# leddriverx3.net
KiCad netlist of a schematic drawn in EAGLE
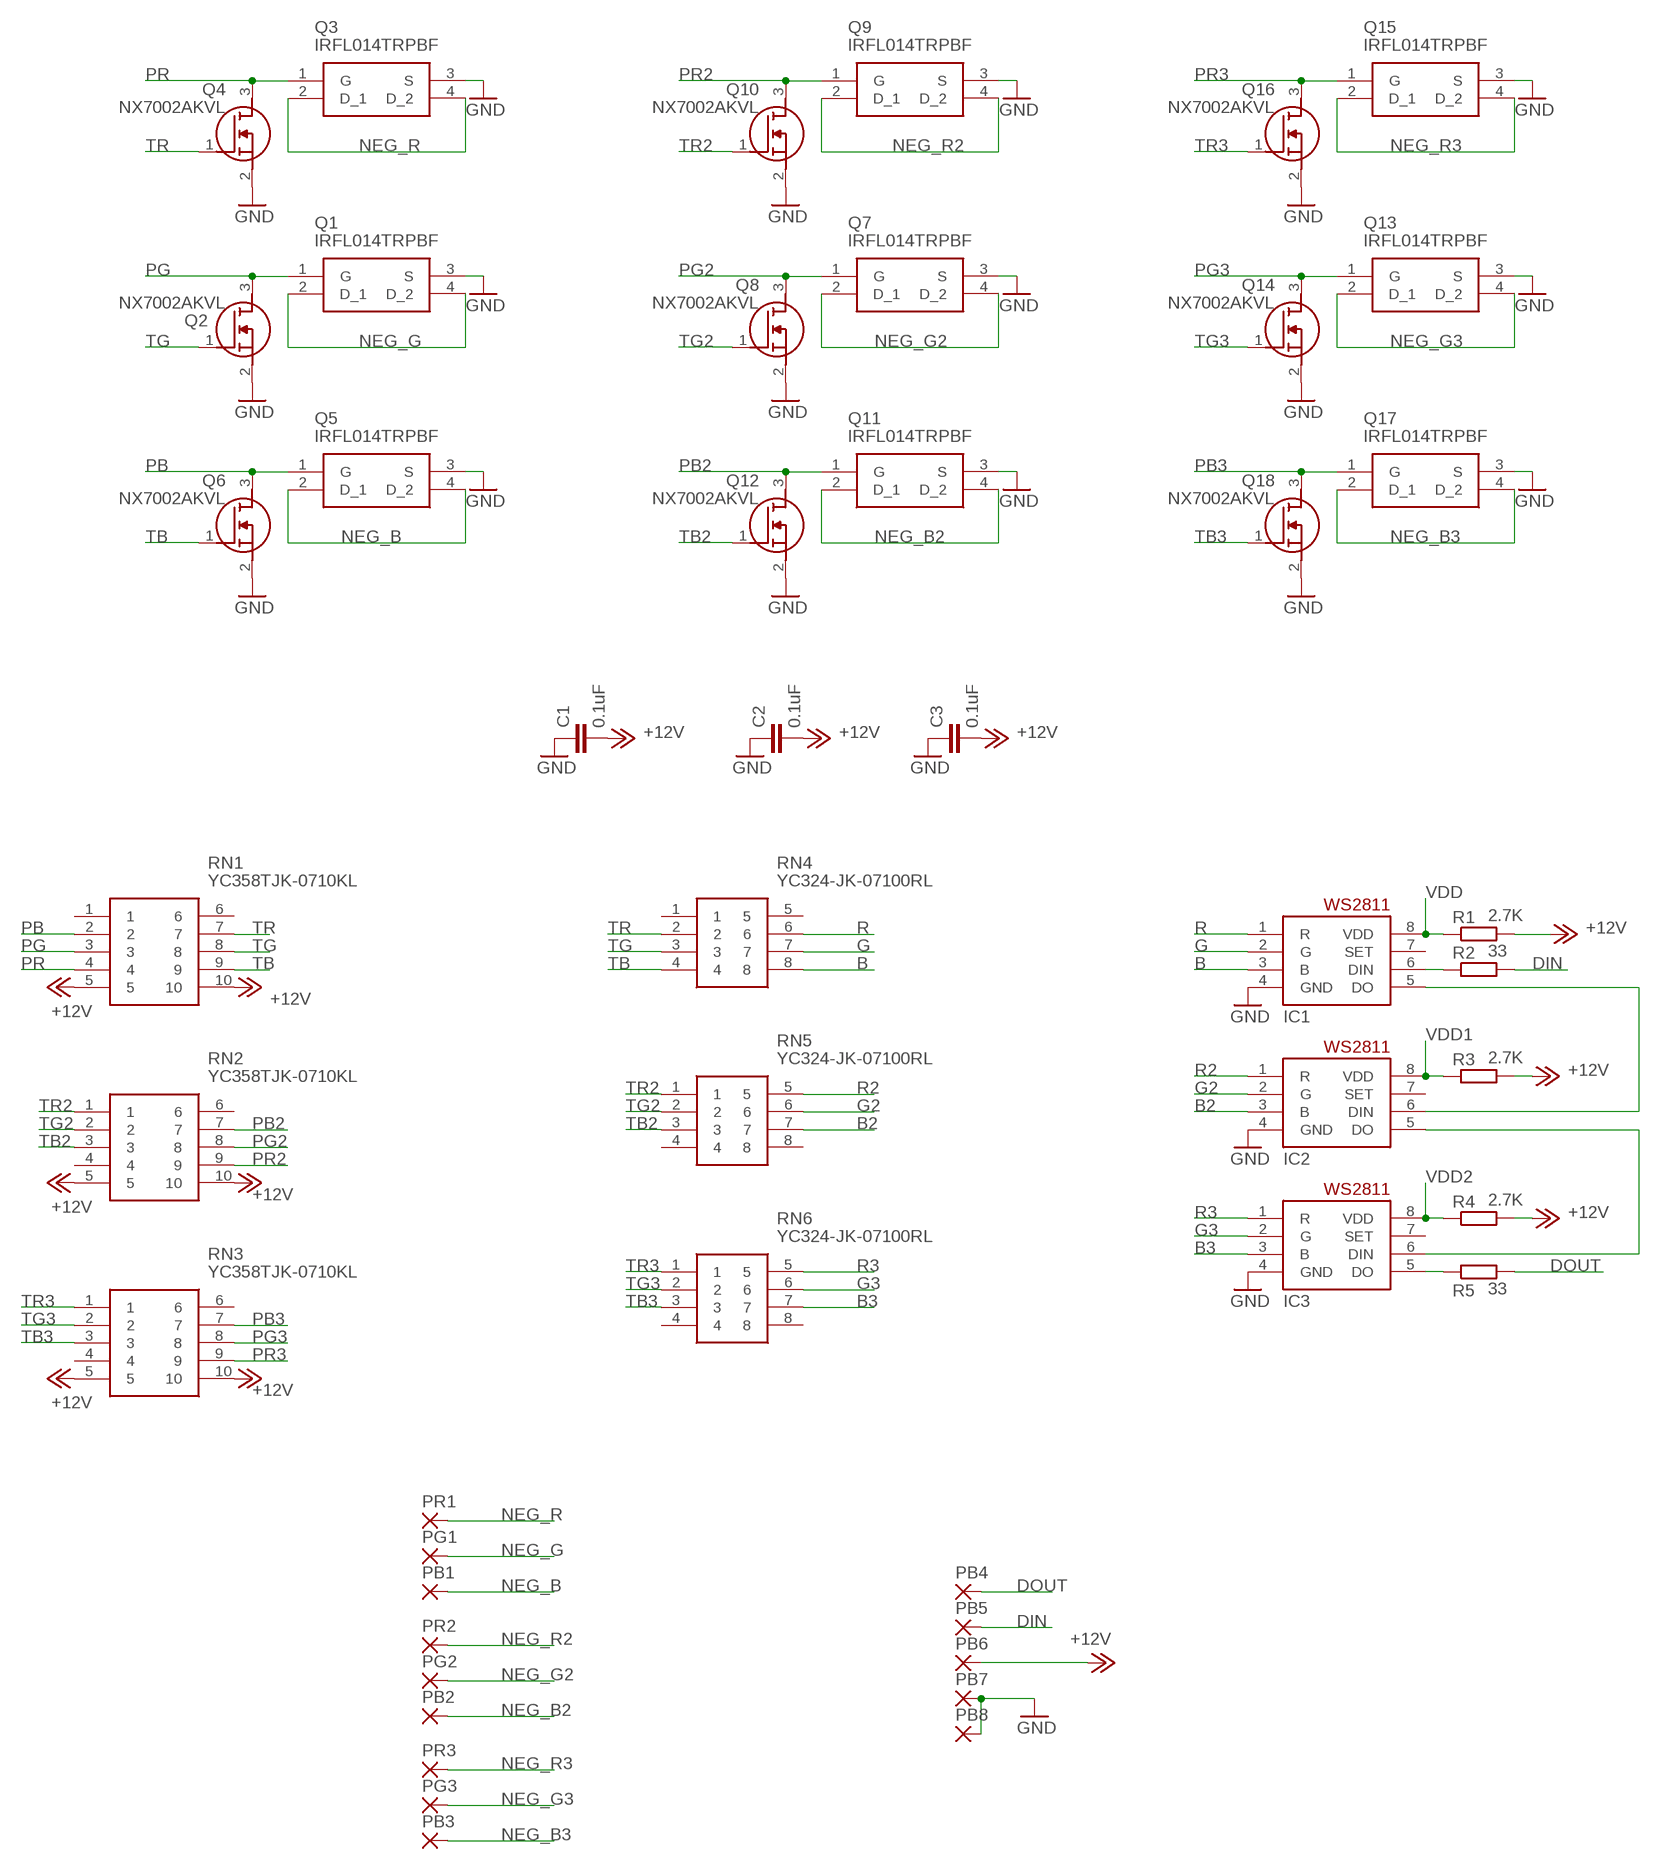
[diagram p0: schematic, sheet 1]

(export (version "E")
  (design (tool "Eeschema 10.0.6"))
  (components
    (comp (ref "C1")
      (value "0.1uF")
      (footprint "eagle-import:C1206")
      (libsource (lib "eagle-import") (part "C-EUC1206"))
    )
    (comp (ref "C2")
      (value "0.1uF")
      (footprint "eagle-import:C1206")
      (libsource (lib "eagle-import") (part "C-EUC1206"))
    )
    (comp (ref "C3")
      (value "0.1uF")
      (footprint "eagle-import:C1206")
      (libsource (lib "eagle-import") (part "C-EUC1206"))
    )
    (comp (ref "IC1")
      (value "WS2811-SOP8")
      (footprint "eagle-import:SO08-SKINNYPADS")
      (libsource (lib "eagle-import") (part "WS2811-SOP8"))
    )
    (comp (ref "IC2")
      (value "WS2811-SOP8")
      (footprint "eagle-import:SO08-SKINNYPADS")
      (libsource (lib "eagle-import") (part "WS2811-SOP8"))
    )
    (comp (ref "IC3")
      (value "WS2811-SOP8")
      (footprint "eagle-import:SO08-SKINNYPADS")
      (libsource (lib "eagle-import") (part "WS2811-SOP8"))
    )
    (comp (ref "PB1")
      (value "3,81/1,4")
      (footprint "eagle-import:3,81_1,4")
      (libsource (lib "eagle-import") (part "3,81/1,4"))
    )
    (comp (ref "PB2")
      (value "3,81/1,4")
      (footprint "eagle-import:3,81_1,4")
      (libsource (lib "eagle-import") (part "3,81/1,4"))
    )
    (comp (ref "PB3")
      (value "3,81/1,4")
      (footprint "eagle-import:3,81_1,4")
      (libsource (lib "eagle-import") (part "3,81/1,4"))
    )
    (comp (ref "PB4")
      (value "3,81/1,4")
      (footprint "eagle-import:3,81_1,4")
      (libsource (lib "eagle-import") (part "3,81/1,4"))
    )
    (comp (ref "PB5")
      (value "3,81/1,4")
      (footprint "eagle-import:3,81_1,4")
      (libsource (lib "eagle-import") (part "3,81/1,4"))
    )
    (comp (ref "PB6")
      (value "3,81/1,4")
      (footprint "eagle-import:3,81_1,4")
      (libsource (lib "eagle-import") (part "3,81/1,4"))
    )
    (comp (ref "PB7")
      (value "3,81/1,4")
      (footprint "eagle-import:3,81_1,4")
      (libsource (lib "eagle-import") (part "3,81/1,4"))
    )
    (comp (ref "PB8")
      (value "3,81/1,4")
      (footprint "eagle-import:3,81_1,4")
      (libsource (lib "eagle-import") (part "3,81/1,4"))
    )
    (comp (ref "PG1")
      (value "3,81/1,4")
      (footprint "eagle-import:3,81_1,4")
      (libsource (lib "eagle-import") (part "3,81/1,4"))
    )
    (comp (ref "PG2")
      (value "3,81/1,4")
      (footprint "eagle-import:3,81_1,4")
      (libsource (lib "eagle-import") (part "3,81/1,4"))
    )
    (comp (ref "PG3")
      (value "3,81/1,4")
      (footprint "eagle-import:3,81_1,4")
      (libsource (lib "eagle-import") (part "3,81/1,4"))
    )
    (comp (ref "PR1")
      (value "3,81/1,4")
      (footprint "eagle-import:3,81_1,4")
      (libsource (lib "eagle-import") (part "3,81/1,4"))
    )
    (comp (ref "PR2")
      (value "3,81/1,4")
      (footprint "eagle-import:3,81_1,4")
      (libsource (lib "eagle-import") (part "3,81/1,4"))
    )
    (comp (ref "PR3")
      (value "3,81/1,4")
      (footprint "eagle-import:3,81_1,4")
      (libsource (lib "eagle-import") (part "3,81/1,4"))
    )
    (comp (ref "Q1")
      (value "IRFL014TRPBF")
      (footprint "eagle-import:SOT230P700X180-4N")
      (fields (field (name "MOUSER_PART_NUMBER") "844-IRFL014TRPBF"))
      (libsource (lib "eagle-import") (part "IRFL014TRPBF"))
    )
    (comp (ref "Q2")
      (value "NX7002AKVL")
      (footprint "eagle-import:SOT95P230X110-3N")
      (fields (field (name "MOUSER_PART_NUMBER") "771-NX7002AKVL"))
      (libsource (lib "eagle-import") (part "NX7002AKVL"))
    )
    (comp (ref "Q3")
      (value "IRFL014TRPBF")
      (footprint "eagle-import:SOT230P700X180-4N")
      (fields (field (name "MOUSER_PART_NUMBER") "844-IRFL014TRPBF"))
      (libsource (lib "eagle-import") (part "IRFL014TRPBF"))
    )
    (comp (ref "Q4")
      (value "NX7002AKVL")
      (footprint "eagle-import:SOT95P230X110-3N")
      (fields (field (name "MOUSER_PART_NUMBER") "771-NX7002AKVL"))
      (libsource (lib "eagle-import") (part "NX7002AKVL"))
    )
    (comp (ref "Q5")
      (value "IRFL014TRPBF")
      (footprint "eagle-import:SOT230P700X180-4N")
      (fields (field (name "MOUSER_PART_NUMBER") "844-IRFL014TRPBF"))
      (libsource (lib "eagle-import") (part "IRFL014TRPBF"))
    )
    (comp (ref "Q6")
      (value "NX7002AKVL")
      (footprint "eagle-import:SOT95P230X110-3N")
      (fields (field (name "MOUSER_PART_NUMBER") "771-NX7002AKVL"))
      (libsource (lib "eagle-import") (part "NX7002AKVL"))
    )
    (comp (ref "Q7")
      (value "IRFL014TRPBF")
      (footprint "eagle-import:SOT230P700X180-4N")
      (fields (field (name "MOUSER_PART_NUMBER") "844-IRFL014TRPBF"))
      (libsource (lib "eagle-import") (part "IRFL014TRPBF"))
    )
    (comp (ref "Q8")
      (value "NX7002AKVL")
      (footprint "eagle-import:SOT95P230X110-3N")
      (fields (field (name "MOUSER_PART_NUMBER") "771-NX7002AKVL"))
      (libsource (lib "eagle-import") (part "NX7002AKVL"))
    )
    (comp (ref "Q9")
      (value "IRFL014TRPBF")
      (footprint "eagle-import:SOT230P700X180-4N")
      (fields (field (name "MOUSER_PART_NUMBER") "844-IRFL014TRPBF"))
      (libsource (lib "eagle-import") (part "IRFL014TRPBF"))
    )
    (comp (ref "Q10")
      (value "NX7002AKVL")
      (footprint "eagle-import:SOT95P230X110-3N")
      (fields (field (name "MOUSER_PART_NUMBER") "771-NX7002AKVL"))
      (libsource (lib "eagle-import") (part "NX7002AKVL"))
    )
    (comp (ref "Q11")
      (value "IRFL014TRPBF")
      (footprint "eagle-import:SOT230P700X180-4N")
      (fields (field (name "MOUSER_PART_NUMBER") "844-IRFL014TRPBF"))
      (libsource (lib "eagle-import") (part "IRFL014TRPBF"))
    )
    (comp (ref "Q12")
      (value "NX7002AKVL")
      (footprint "eagle-import:SOT95P230X110-3N")
      (fields (field (name "MOUSER_PART_NUMBER") "771-NX7002AKVL"))
      (libsource (lib "eagle-import") (part "NX7002AKVL"))
    )
    (comp (ref "Q13")
      (value "IRFL014TRPBF")
      (footprint "eagle-import:SOT230P700X180-4N")
      (fields (field (name "MOUSER_PART_NUMBER") "844-IRFL014TRPBF"))
      (libsource (lib "eagle-import") (part "IRFL014TRPBF"))
    )
    (comp (ref "Q14")
      (value "NX7002AKVL")
      (footprint "eagle-import:SOT95P230X110-3N")
      (fields (field (name "MOUSER_PART_NUMBER") "771-NX7002AKVL"))
      (libsource (lib "eagle-import") (part "NX7002AKVL"))
    )
    (comp (ref "Q15")
      (value "IRFL014TRPBF")
      (footprint "eagle-import:SOT230P700X180-4N")
      (fields (field (name "MOUSER_PART_NUMBER") "844-IRFL014TRPBF"))
      (libsource (lib "eagle-import") (part "IRFL014TRPBF"))
    )
    (comp (ref "Q16")
      (value "NX7002AKVL")
      (footprint "eagle-import:SOT95P230X110-3N")
      (fields (field (name "MOUSER_PART_NUMBER") "771-NX7002AKVL"))
      (libsource (lib "eagle-import") (part "NX7002AKVL"))
    )
    (comp (ref "Q17")
      (value "IRFL014TRPBF")
      (footprint "eagle-import:SOT230P700X180-4N")
      (fields (field (name "MOUSER_PART_NUMBER") "844-IRFL014TRPBF"))
      (libsource (lib "eagle-import") (part "IRFL014TRPBF"))
    )
    (comp (ref "Q18")
      (value "NX7002AKVL")
      (footprint "eagle-import:SOT95P230X110-3N")
      (fields (field (name "MOUSER_PART_NUMBER") "771-NX7002AKVL"))
      (libsource (lib "eagle-import") (part "NX7002AKVL"))
    )
    (comp (ref "R1")
      (value "2.7K")
      (footprint "eagle-import:R1206")
      (libsource (lib "eagle-import") (part "R-EU_R1206"))
    )
    (comp (ref "R2")
      (value "33")
      (footprint "eagle-import:R1206")
      (libsource (lib "eagle-import") (part "R-EU_R1206"))
    )
    (comp (ref "R3")
      (value "2.7K")
      (footprint "eagle-import:R1206")
      (libsource (lib "eagle-import") (part "R-EU_R1206"))
    )
    (comp (ref "R4")
      (value "2.7K")
      (footprint "eagle-import:R1206")
      (libsource (lib "eagle-import") (part "R-EU_R1206"))
    )
    (comp (ref "R5")
      (value "33")
      (footprint "eagle-import:R1206")
      (libsource (lib "eagle-import") (part "R-EU_R1206"))
    )
    (comp (ref "RN1")
      (value "YC358TJK-0710KL")
      (footprint "eagle-import:YC358T")
      (fields (field (name "MOUSER_PART_NUMBER") "603-YC358TJK-0710KL"))
      (libsource (lib "eagle-import") (part "YC358TJK-0710KL"))
    )
    (comp (ref "RN2")
      (value "YC358TJK-0710KL")
      (footprint "eagle-import:YC358T")
      (fields (field (name "MOUSER_PART_NUMBER") "603-YC358TJK-0710KL"))
      (libsource (lib "eagle-import") (part "YC358TJK-0710KL"))
    )
    (comp (ref "RN3")
      (value "YC358TJK-0710KL")
      (footprint "eagle-import:YC358T")
      (fields (field (name "MOUSER_PART_NUMBER") "603-YC358TJK-0710KL"))
      (libsource (lib "eagle-import") (part "YC358TJK-0710KL"))
    )
    (comp (ref "RN4")
      (value "YC324-JK-07100RL")
      (footprint "eagle-import:YC324JK07100RL")
      (fields (field (name "MOUSER_PART_NUMBER") "603-YC324-JK-07100RL"))
      (libsource (lib "eagle-import") (part "YC324-JK-07100RL"))
    )
    (comp (ref "RN5")
      (value "YC324-JK-07100RL")
      (footprint "eagle-import:YC324JK07100RL")
      (fields (field (name "MOUSER_PART_NUMBER") "603-YC324-JK-07100RL"))
      (libsource (lib "eagle-import") (part "YC324-JK-07100RL"))
    )
    (comp (ref "RN6")
      (value "YC324-JK-07100RL")
      (footprint "eagle-import:YC324JK07100RL")
      (fields (field (name "MOUSER_PART_NUMBER") "603-YC324-JK-07100RL"))
      (libsource (lib "eagle-import") (part "YC324-JK-07100RL"))
    )
  )
  (nets
    (net (code "1") (name "+12V") (class "Default")
      (node (ref "C1") (pin "2") (pinfunction "2_2") (pintype "passive"))
      (node (ref "C2") (pin "2") (pinfunction "2_2") (pintype "passive"))
      (node (ref "C3") (pin "2") (pinfunction "2_2") (pintype "passive"))
      (node (ref "PB6") (pin "1") (pinfunction "P_1") (pintype "passive"))
      (node (ref "R1") (pin "2") (pinfunction "2_2") (pintype "passive"))
      (node (ref "R3") (pin "2") (pinfunction "2_2") (pintype "passive"))
      (node (ref "R4") (pin "2") (pinfunction "2_2") (pintype "passive"))
      (node (ref "RN1") (pin "10") (pinfunction "10_10") (pintype "bidirectional"))
      (node (ref "RN1") (pin "5") (pinfunction "5_5") (pintype "bidirectional"))
      (node (ref "RN2") (pin "10") (pinfunction "10_10") (pintype "bidirectional"))
      (node (ref "RN2") (pin "5") (pinfunction "5_5") (pintype "bidirectional"))
      (node (ref "RN3") (pin "10") (pinfunction "10_10") (pintype "bidirectional"))
      (node (ref "RN3") (pin "5") (pinfunction "5_5") (pintype "bidirectional"))
    )
    (net (code "2") (name "/B") (class "Default")
      (node (ref "IC1") (pin "3") (pinfunction "B_3") (pintype "open_collector"))
      (node (ref "RN4") (pin "8") (pinfunction "8_8") (pintype "bidirectional"))
    )
    (net (code "3") (name "/B2") (class "Default")
      (node (ref "IC2") (pin "3") (pinfunction "B_3") (pintype "open_collector"))
      (node (ref "RN5") (pin "7") (pinfunction "7_7") (pintype "bidirectional"))
    )
    (net (code "4") (name "/B3") (class "Default")
      (node (ref "IC3") (pin "3") (pinfunction "B_3") (pintype "open_collector"))
      (node (ref "RN6") (pin "7") (pinfunction "7_7") (pintype "bidirectional"))
    )
    (net (code "5") (name "/DIN") (class "Default")
      (node (ref "PB5") (pin "1") (pinfunction "P_1") (pintype "passive"))
      (node (ref "R2") (pin "2") (pinfunction "2_2") (pintype "passive"))
    )
    (net (code "6") (name "/DOUT") (class "Default")
      (node (ref "PB4") (pin "1") (pinfunction "P_1") (pintype "passive"))
      (node (ref "R5") (pin "2") (pinfunction "2_2") (pintype "passive"))
    )
    (net (code "7") (name "/G") (class "Default")
      (node (ref "IC1") (pin "2") (pinfunction "G_2") (pintype "open_collector"))
      (node (ref "RN4") (pin "7") (pinfunction "7_7") (pintype "bidirectional"))
    )
    (net (code "8") (name "/G2") (class "Default")
      (node (ref "IC2") (pin "2") (pinfunction "G_2") (pintype "open_collector"))
      (node (ref "RN5") (pin "6") (pinfunction "6_6") (pintype "bidirectional"))
    )
    (net (code "9") (name "/G3") (class "Default")
      (node (ref "IC3") (pin "2") (pinfunction "G_2") (pintype "open_collector"))
      (node (ref "RN6") (pin "6") (pinfunction "6_6") (pintype "bidirectional"))
    )
    (net (code "10") (name "/NEG_B") (class "Default")
      (node (ref "PB1") (pin "1") (pinfunction "P_1") (pintype "passive"))
      (node (ref "Q5") (pin "2") (pinfunction "D_1_2") (pintype "bidirectional"))
      (node (ref "Q5") (pin "4") (pinfunction "D_2_4") (pintype "bidirectional"))
    )
    (net (code "11") (name "/NEG_B2") (class "Default")
      (node (ref "PB2") (pin "1") (pinfunction "P_1") (pintype "passive"))
      (node (ref "Q11") (pin "2") (pinfunction "D_1_2") (pintype "bidirectional"))
      (node (ref "Q11") (pin "4") (pinfunction "D_2_4") (pintype "bidirectional"))
    )
    (net (code "12") (name "/NEG_B3") (class "Default")
      (node (ref "PB3") (pin "1") (pinfunction "P_1") (pintype "passive"))
      (node (ref "Q17") (pin "2") (pinfunction "D_1_2") (pintype "bidirectional"))
      (node (ref "Q17") (pin "4") (pinfunction "D_2_4") (pintype "bidirectional"))
    )
    (net (code "13") (name "/NEG_G") (class "Default")
      (node (ref "PG1") (pin "1") (pinfunction "P_1") (pintype "passive"))
      (node (ref "Q1") (pin "2") (pinfunction "D_1_2") (pintype "bidirectional"))
      (node (ref "Q1") (pin "4") (pinfunction "D_2_4") (pintype "bidirectional"))
    )
    (net (code "14") (name "/NEG_G2") (class "Default")
      (node (ref "PG2") (pin "1") (pinfunction "P_1") (pintype "passive"))
      (node (ref "Q7") (pin "2") (pinfunction "D_1_2") (pintype "bidirectional"))
      (node (ref "Q7") (pin "4") (pinfunction "D_2_4") (pintype "bidirectional"))
    )
    (net (code "15") (name "/NEG_G3") (class "Default")
      (node (ref "PG3") (pin "1") (pinfunction "P_1") (pintype "passive"))
      (node (ref "Q13") (pin "2") (pinfunction "D_1_2") (pintype "bidirectional"))
      (node (ref "Q13") (pin "4") (pinfunction "D_2_4") (pintype "bidirectional"))
    )
    (net (code "16") (name "/NEG_R") (class "Default")
      (node (ref "PR1") (pin "1") (pinfunction "P_1") (pintype "passive"))
      (node (ref "Q3") (pin "2") (pinfunction "D_1_2") (pintype "bidirectional"))
      (node (ref "Q3") (pin "4") (pinfunction "D_2_4") (pintype "bidirectional"))
    )
    (net (code "17") (name "/NEG_R2") (class "Default")
      (node (ref "PR2") (pin "1") (pinfunction "P_1") (pintype "passive"))
      (node (ref "Q9") (pin "2") (pinfunction "D_1_2") (pintype "bidirectional"))
      (node (ref "Q9") (pin "4") (pinfunction "D_2_4") (pintype "bidirectional"))
    )
    (net (code "18") (name "/NEG_R3") (class "Default")
      (node (ref "PR3") (pin "1") (pinfunction "P_1") (pintype "passive"))
      (node (ref "Q15") (pin "2") (pinfunction "D_1_2") (pintype "bidirectional"))
      (node (ref "Q15") (pin "4") (pinfunction "D_2_4") (pintype "bidirectional"))
    )
    (net (code "19") (name "/PB") (class "Default")
      (node (ref "Q5") (pin "1") (pinfunction "G_1") (pintype "bidirectional"))
      (node (ref "Q6") (pin "3") (pinfunction "D_3") (pintype "bidirectional"))
      (node (ref "RN1") (pin "2") (pinfunction "2_2") (pintype "bidirectional"))
    )
    (net (code "20") (name "/PB2") (class "Default")
      (node (ref "Q11") (pin "1") (pinfunction "G_1") (pintype "bidirectional"))
      (node (ref "Q12") (pin "3") (pinfunction "D_3") (pintype "bidirectional"))
      (node (ref "RN2") (pin "7") (pinfunction "7_7") (pintype "bidirectional"))
    )
    (net (code "21") (name "/PB3") (class "Default")
      (node (ref "Q17") (pin "1") (pinfunction "G_1") (pintype "bidirectional"))
      (node (ref "Q18") (pin "3") (pinfunction "D_3") (pintype "bidirectional"))
      (node (ref "RN3") (pin "7") (pinfunction "7_7") (pintype "bidirectional"))
    )
    (net (code "22") (name "/PG") (class "Default")
      (node (ref "Q1") (pin "1") (pinfunction "G_1") (pintype "bidirectional"))
      (node (ref "Q2") (pin "3") (pinfunction "D_3") (pintype "bidirectional"))
      (node (ref "RN1") (pin "3") (pinfunction "3_3") (pintype "bidirectional"))
    )
    (net (code "23") (name "/PG2") (class "Default")
      (node (ref "Q7") (pin "1") (pinfunction "G_1") (pintype "bidirectional"))
      (node (ref "Q8") (pin "3") (pinfunction "D_3") (pintype "bidirectional"))
      (node (ref "RN2") (pin "8") (pinfunction "8_8") (pintype "bidirectional"))
    )
    (net (code "24") (name "/PG3") (class "Default")
      (node (ref "Q13") (pin "1") (pinfunction "G_1") (pintype "bidirectional"))
      (node (ref "Q14") (pin "3") (pinfunction "D_3") (pintype "bidirectional"))
      (node (ref "RN3") (pin "8") (pinfunction "8_8") (pintype "bidirectional"))
    )
    (net (code "25") (name "/PR") (class "Default")
      (node (ref "Q3") (pin "1") (pinfunction "G_1") (pintype "bidirectional"))
      (node (ref "Q4") (pin "3") (pinfunction "D_3") (pintype "bidirectional"))
      (node (ref "RN1") (pin "4") (pinfunction "4_4") (pintype "bidirectional"))
    )
    (net (code "26") (name "/PR2") (class "Default")
      (node (ref "Q10") (pin "3") (pinfunction "D_3") (pintype "bidirectional"))
      (node (ref "Q9") (pin "1") (pinfunction "G_1") (pintype "bidirectional"))
      (node (ref "RN2") (pin "9") (pinfunction "9_9") (pintype "bidirectional"))
    )
    (net (code "27") (name "/PR3") (class "Default")
      (node (ref "Q15") (pin "1") (pinfunction "G_1") (pintype "bidirectional"))
      (node (ref "Q16") (pin "3") (pinfunction "D_3") (pintype "bidirectional"))
      (node (ref "RN3") (pin "9") (pinfunction "9_9") (pintype "bidirectional"))
    )
    (net (code "28") (name "/R") (class "Default")
      (node (ref "IC1") (pin "1") (pinfunction "R_1") (pintype "open_collector"))
      (node (ref "RN4") (pin "6") (pinfunction "6_6") (pintype "bidirectional"))
    )
    (net (code "29") (name "/R2") (class "Default")
      (node (ref "IC2") (pin "1") (pinfunction "R_1") (pintype "open_collector"))
      (node (ref "RN5") (pin "5") (pinfunction "5_5") (pintype "bidirectional"))
    )
    (net (code "30") (name "/R3") (class "Default")
      (node (ref "IC3") (pin "1") (pinfunction "R_1") (pintype "open_collector"))
      (node (ref "RN6") (pin "5") (pinfunction "5_5") (pintype "bidirectional"))
    )
    (net (code "31") (name "/TB") (class "Default")
      (node (ref "Q6") (pin "1") (pinfunction "G_1") (pintype "bidirectional"))
      (node (ref "RN1") (pin "9") (pinfunction "9_9") (pintype "bidirectional"))
      (node (ref "RN4") (pin "4") (pinfunction "4_4") (pintype "bidirectional"))
    )
    (net (code "32") (name "/TB2") (class "Default")
      (node (ref "Q12") (pin "1") (pinfunction "G_1") (pintype "bidirectional"))
      (node (ref "RN2") (pin "3") (pinfunction "3_3") (pintype "bidirectional"))
      (node (ref "RN5") (pin "3") (pinfunction "3_3") (pintype "bidirectional"))
    )
    (net (code "33") (name "/TB3") (class "Default")
      (node (ref "Q18") (pin "1") (pinfunction "G_1") (pintype "bidirectional"))
      (node (ref "RN3") (pin "3") (pinfunction "3_3") (pintype "bidirectional"))
      (node (ref "RN6") (pin "3") (pinfunction "3_3") (pintype "bidirectional"))
    )
    (net (code "34") (name "/TG") (class "Default")
      (node (ref "Q2") (pin "1") (pinfunction "G_1") (pintype "bidirectional"))
      (node (ref "RN1") (pin "8") (pinfunction "8_8") (pintype "bidirectional"))
      (node (ref "RN4") (pin "3") (pinfunction "3_3") (pintype "bidirectional"))
    )
    (net (code "35") (name "/TG2") (class "Default")
      (node (ref "Q8") (pin "1") (pinfunction "G_1") (pintype "bidirectional"))
      (node (ref "RN2") (pin "2") (pinfunction "2_2") (pintype "bidirectional"))
      (node (ref "RN5") (pin "2") (pinfunction "2_2") (pintype "bidirectional"))
    )
    (net (code "36") (name "/TG3") (class "Default")
      (node (ref "Q14") (pin "1") (pinfunction "G_1") (pintype "bidirectional"))
      (node (ref "RN3") (pin "2") (pinfunction "2_2") (pintype "bidirectional"))
      (node (ref "RN6") (pin "2") (pinfunction "2_2") (pintype "bidirectional"))
    )
    (net (code "37") (name "/TR") (class "Default")
      (node (ref "Q4") (pin "1") (pinfunction "G_1") (pintype "bidirectional"))
      (node (ref "RN1") (pin "7") (pinfunction "7_7") (pintype "bidirectional"))
      (node (ref "RN4") (pin "2") (pinfunction "2_2") (pintype "bidirectional"))
    )
    (net (code "38") (name "/TR2") (class "Default")
      (node (ref "Q10") (pin "1") (pinfunction "G_1") (pintype "bidirectional"))
      (node (ref "RN2") (pin "1") (pinfunction "1_1") (pintype "bidirectional"))
      (node (ref "RN5") (pin "1") (pinfunction "1_1") (pintype "bidirectional"))
    )
    (net (code "39") (name "/TR3") (class "Default")
      (node (ref "Q16") (pin "1") (pinfunction "G_1") (pintype "bidirectional"))
      (node (ref "RN3") (pin "1") (pinfunction "1_1") (pintype "bidirectional"))
      (node (ref "RN6") (pin "1") (pinfunction "1_1") (pintype "bidirectional"))
    )
    (net (code "40") (name "/VDD") (class "Default")
      (node (ref "IC1") (pin "8") (pinfunction "VDD_8") (pintype "power_in"))
      (node (ref "R1") (pin "1") (pinfunction "1_1") (pintype "passive"))
    )
    (net (code "41") (name "/VDD1") (class "Default")
      (node (ref "IC2") (pin "8") (pinfunction "VDD_8") (pintype "power_in"))
      (node (ref "R3") (pin "1") (pinfunction "1_1") (pintype "passive"))
    )
    (net (code "42") (name "/VDD2") (class "Default")
      (node (ref "IC3") (pin "8") (pinfunction "VDD_8") (pintype "power_in"))
      (node (ref "R4") (pin "1") (pinfunction "1_1") (pintype "passive"))
    )
    (net (code "43") (name "GND") (class "Default")
      (node (ref "C1") (pin "1") (pinfunction "1_1") (pintype "passive"))
      (node (ref "C2") (pin "1") (pinfunction "1_1") (pintype "passive"))
      (node (ref "C3") (pin "1") (pinfunction "1_1") (pintype "passive"))
      (node (ref "IC1") (pin "4") (pinfunction "GND_4") (pintype "power_in"))
      (node (ref "IC2") (pin "4") (pinfunction "GND_4") (pintype "power_in"))
      (node (ref "IC3") (pin "4") (pinfunction "GND_4") (pintype "power_in"))
      (node (ref "PB7") (pin "1") (pinfunction "P_1") (pintype "passive"))
      (node (ref "PB8") (pin "1") (pinfunction "P_1") (pintype "passive"))
      (node (ref "Q1") (pin "3") (pinfunction "S_3") (pintype "bidirectional"))
      (node (ref "Q10") (pin "2") (pinfunction "S_2") (pintype "bidirectional"))
      (node (ref "Q11") (pin "3") (pinfunction "S_3") (pintype "bidirectional"))
      (node (ref "Q12") (pin "2") (pinfunction "S_2") (pintype "bidirectional"))
      (node (ref "Q13") (pin "3") (pinfunction "S_3") (pintype "bidirectional"))
      (node (ref "Q14") (pin "2") (pinfunction "S_2") (pintype "bidirectional"))
      (node (ref "Q15") (pin "3") (pinfunction "S_3") (pintype "bidirectional"))
      (node (ref "Q16") (pin "2") (pinfunction "S_2") (pintype "bidirectional"))
      (node (ref "Q17") (pin "3") (pinfunction "S_3") (pintype "bidirectional"))
      (node (ref "Q18") (pin "2") (pinfunction "S_2") (pintype "bidirectional"))
      (node (ref "Q2") (pin "2") (pinfunction "S_2") (pintype "bidirectional"))
      (node (ref "Q3") (pin "3") (pinfunction "S_3") (pintype "bidirectional"))
      (node (ref "Q4") (pin "2") (pinfunction "S_2") (pintype "bidirectional"))
      (node (ref "Q5") (pin "3") (pinfunction "S_3") (pintype "bidirectional"))
      (node (ref "Q6") (pin "2") (pinfunction "S_2") (pintype "bidirectional"))
      (node (ref "Q7") (pin "3") (pinfunction "S_3") (pintype "bidirectional"))
      (node (ref "Q8") (pin "2") (pinfunction "S_2") (pintype "bidirectional"))
      (node (ref "Q9") (pin "3") (pinfunction "S_3") (pintype "bidirectional"))
    )
    (net (code "44") (name "Net-(IC1-DIN)") (class "Default")
      (node (ref "IC1") (pin "6") (pinfunction "DIN_6") (pintype "input"))
      (node (ref "R2") (pin "1") (pinfunction "1_1") (pintype "passive"))
    )
    (net (code "45") (name "Net-(IC1-DO)") (class "Default")
      (node (ref "IC1") (pin "5") (pinfunction "DO_5") (pintype "output"))
      (node (ref "IC2") (pin "6") (pinfunction "DIN_6") (pintype "input"))
    )
    (net (code "46") (name "Net-(IC2-DO)") (class "Default")
      (node (ref "IC2") (pin "5") (pinfunction "DO_5") (pintype "output"))
      (node (ref "IC3") (pin "6") (pinfunction "DIN_6") (pintype "input"))
    )
    (net (code "47") (name "Net-(IC3-DO)") (class "Default")
      (node (ref "IC3") (pin "5") (pinfunction "DO_5") (pintype "output"))
      (node (ref "R5") (pin "1") (pinfunction "1_1") (pintype "passive"))
    )
    (net (code "48") (name "unconnected-(IC1-SET-Pad7)") (class "Default")
      (node (ref "IC1") (pin "7") (pinfunction "SET_7") (pintype "input"))
    )
    (net (code "49") (name "unconnected-(IC2-SET-Pad7)") (class "Default")
      (node (ref "IC2") (pin "7") (pinfunction "SET_7") (pintype "input"))
    )
    (net (code "50") (name "unconnected-(IC3-SET-Pad7)") (class "Default")
      (node (ref "IC3") (pin "7") (pinfunction "SET_7") (pintype "input"))
    )
    (net (code "51") (name "unconnected-(RN1-Pad1)") (class "Default")
      (node (ref "RN1") (pin "1") (pinfunction "1_1") (pintype "bidirectional"))
    )
    (net (code "52") (name "unconnected-(RN1-Pad6)") (class "Default")
      (node (ref "RN1") (pin "6") (pinfunction "6_6") (pintype "bidirectional"))
    )
    (net (code "53") (name "unconnected-(RN2-Pad4)") (class "Default")
      (node (ref "RN2") (pin "4") (pinfunction "4_4") (pintype "bidirectional"))
    )
    (net (code "54") (name "unconnected-(RN2-Pad6)") (class "Default")
      (node (ref "RN2") (pin "6") (pinfunction "6_6") (pintype "bidirectional"))
    )
    (net (code "55") (name "unconnected-(RN3-Pad4)") (class "Default")
      (node (ref "RN3") (pin "4") (pinfunction "4_4") (pintype "bidirectional"))
    )
    (net (code "56") (name "unconnected-(RN3-Pad6)") (class "Default")
      (node (ref "RN3") (pin "6") (pinfunction "6_6") (pintype "bidirectional"))
    )
    (net (code "57") (name "unconnected-(RN4-Pad1)") (class "Default")
      (node (ref "RN4") (pin "1") (pinfunction "1_1") (pintype "bidirectional"))
    )
    (net (code "58") (name "unconnected-(RN4-Pad5)") (class "Default")
      (node (ref "RN4") (pin "5") (pinfunction "5_5") (pintype "bidirectional"))
    )
    (net (code "59") (name "unconnected-(RN5-Pad4)") (class "Default")
      (node (ref "RN5") (pin "4") (pinfunction "4_4") (pintype "bidirectional"))
    )
    (net (code "60") (name "unconnected-(RN5-Pad8)") (class "Default")
      (node (ref "RN5") (pin "8") (pinfunction "8_8") (pintype "bidirectional"))
    )
    (net (code "61") (name "unconnected-(RN6-Pad4)") (class "Default")
      (node (ref "RN6") (pin "4") (pinfunction "4_4") (pintype "bidirectional"))
    )
    (net (code "62") (name "unconnected-(RN6-Pad8)") (class "Default")
      (node (ref "RN6") (pin "8") (pinfunction "8_8") (pintype "bidirectional"))
    )
  )
)
